# ICM-42670-P_IMU.net
KiCad netlist of a schematic drawn in Altium Designer
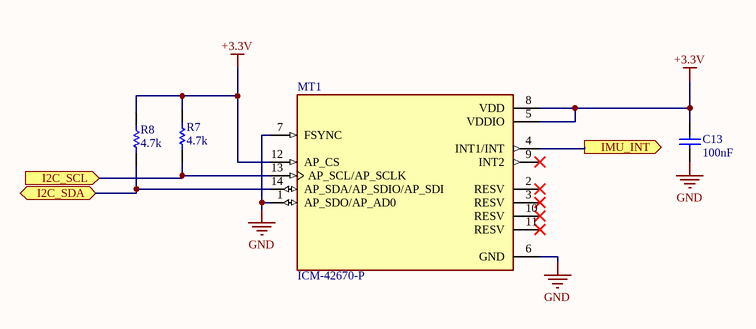
[diagram p0: ICM-42670-P_IMU.SchDoc]

(export (version "E")
  (design (tool "Eeschema 10.0.6"))
  (components
    (comp (ref "C13")
      (value "100nF")
      (footprint "CAPC1005X55N")
      (description "Capacitor")
      (fields (field (name "Comment") "Cap") (field (name "PUBLISHER") "Altium Limited"))
      (libsource (lib "Miscellaneous Devices") (part "Cap"))
    )
    (comp (ref "MT1")
      (value "ICM-42670-P")
      (footprint "XDCR_ICM-42670-P")
      (libsource (lib "ICM-42670-P") (part "ICM-42670-P"))
    )
    (comp (ref "R7")
      (value "4.7k")
      (footprint "RESC1005X40")
      (description "Resistor")
      (fields (field (name "Comment") "Res1") (field (name "PUBLISHER") "Altium Limited"))
      (libsource (lib "Miscellaneous Devices") (part "Res1"))
    )
    (comp (ref "R8")
      (value "4.7k")
      (footprint "RESC1005X40")
      (description "Resistor")
      (fields (field (name "Comment") "Res1") (field (name "PUBLISHER") "Altium Limited"))
      (libsource (lib "Miscellaneous Devices") (part "Res1"))
    )
  )
  (nets
    (net (code "1") (name "+3.3V") (class "Default")
      (node (ref "C13") (pin "2") (pinfunction "2_2") (pintype "passive"))
      (node (ref "MT1") (pin "12") (pinfunction "AP_CS_12") (pintype "input"))
      (node (ref "MT1") (pin "5") (pinfunction "VDDIO_5") (pintype "power_in"))
      (node (ref "MT1") (pin "8") (pinfunction "VDD_8") (pintype "power_in"))
      (node (ref "R7") (pin "2") (pinfunction "2_2") (pintype "passive"))
      (node (ref "R8") (pin "2") (pinfunction "2_2") (pintype "passive"))
    )
    (net (code "2") (name "/I2C_SCL") (class "Default")
      (node (ref "MT1") (pin "13") (pinfunction "AP_SCL/AP_SCLK_13") (pintype "input"))
      (node (ref "R7") (pin "1") (pinfunction "1_1") (pintype "passive"))
    )
    (net (code "3") (name "/I2C_SDA") (class "Default")
      (node (ref "MT1") (pin "14") (pinfunction "AP_SDA/AP_SDIO/AP_SDI_14") (pintype "bidirectional"))
      (node (ref "R8") (pin "1") (pinfunction "1_1") (pintype "passive"))
    )
    (net (code "4") (name "/IMU_INT") (class "Default")
      (node (ref "MT1") (pin "4") (pinfunction "INT1/INT_4") (pintype "output"))
    )
    (net (code "5") (name "GND") (class "Default")
      (node (ref "C13") (pin "1") (pinfunction "1_1") (pintype "passive"))
      (node (ref "MT1") (pin "1") (pinfunction "AP_SDO/AP_AD0_1") (pintype "bidirectional"))
      (node (ref "MT1") (pin "6") (pinfunction "GND_6") (pintype "power_in"))
      (node (ref "MT1") (pin "7") (pinfunction "FSYNC_7") (pintype "input"))
    )
    (net (code "6") (name "unconnected-(MT1-INT2-Pad9)") (class "Default")
      (node (ref "MT1") (pin "9") (pinfunction "INT2_9") (pintype "output+no_connect"))
    )
    (net (code "7") (name "unconnected-(MT1-RESV-Pad2)") (class "Default")
      (node (ref "MT1") (pin "2") (pinfunction "RESV_2") (pintype "passive+no_connect"))
    )
    (net (code "8") (name "unconnected-(MT1-RESV-Pad3)") (class "Default")
      (node (ref "MT1") (pin "3") (pinfunction "RESV_3") (pintype "passive+no_connect"))
    )
    (net (code "9") (name "unconnected-(MT1-RESV-Pad10)") (class "Default")
      (node (ref "MT1") (pin "10") (pinfunction "RESV_10") (pintype "passive+no_connect"))
    )
    (net (code "10") (name "unconnected-(MT1-RESV-Pad11)") (class "Default")
      (node (ref "MT1") (pin "11") (pinfunction "RESV_11") (pintype "passive+no_connect"))
    )
  )
)
